# pcb.net
KiCad netlist of a schematic drawn in EAGLE
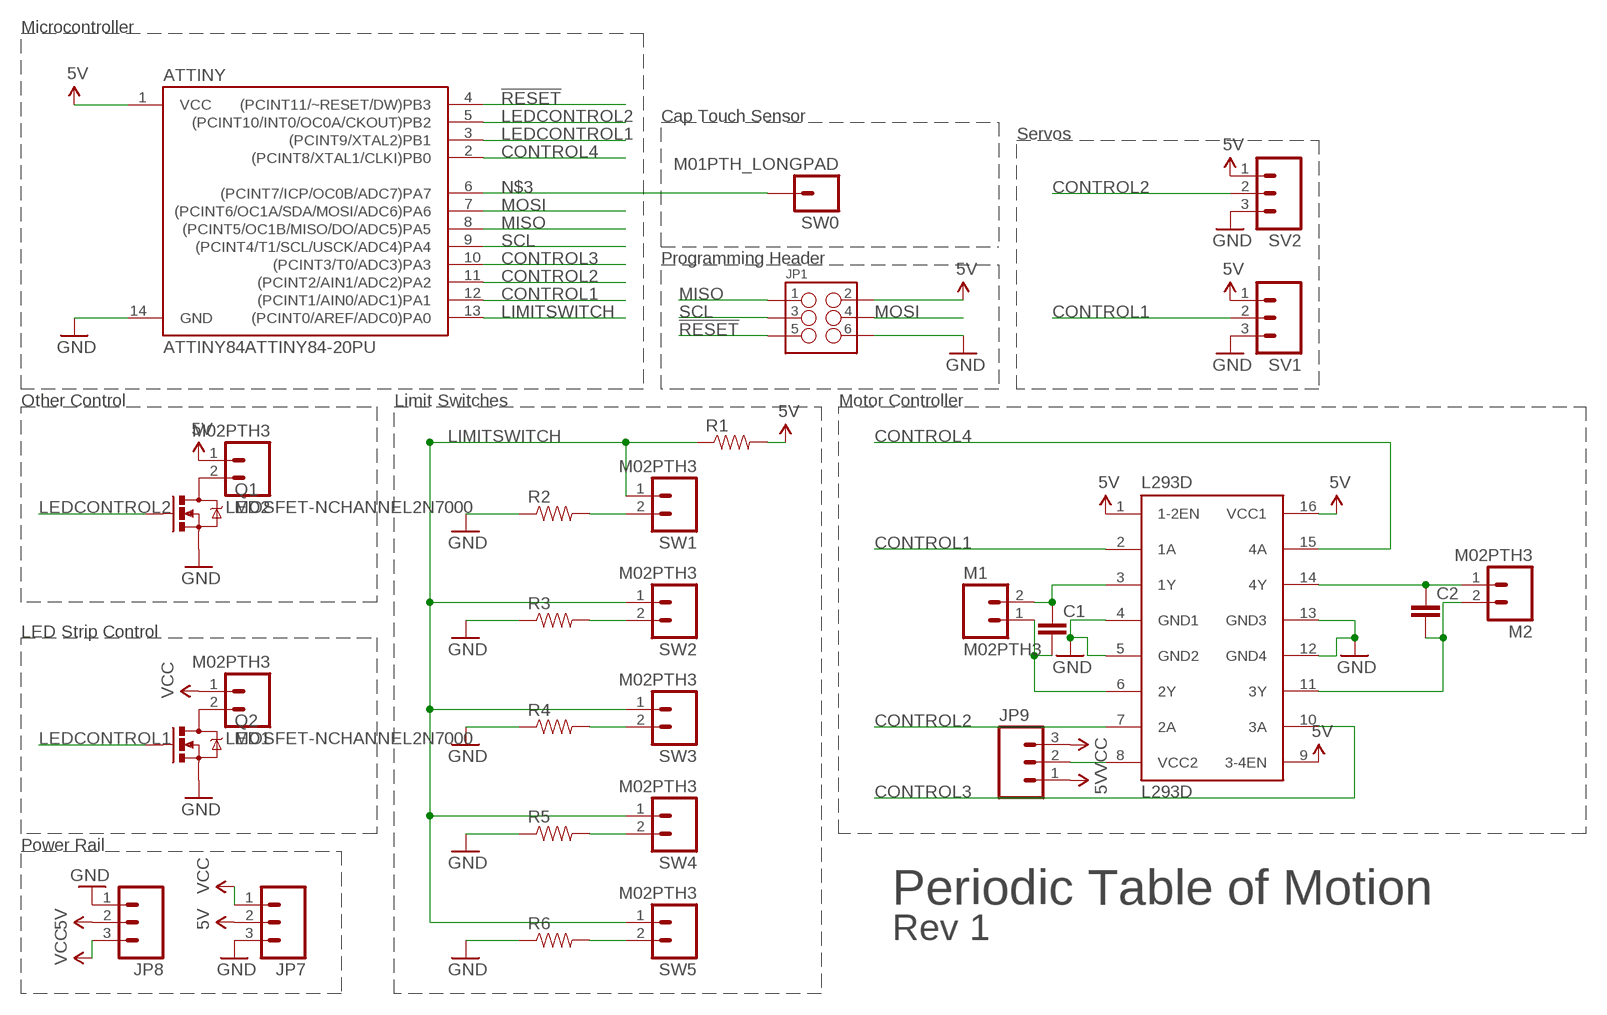
[diagram p0: schematic, sheet 1]

(export (version "E")
  (design (tool "Eeschema 10.0.6"))
  (components
    (comp (ref "ATTINY")
      (value "ATTINY84ATTINY84-20PU")
      (footprint "eagle-import:DIL14")
      (libsource (lib "eagle-import") (part "ATTINY84ATTINY84-20PU"))
    )
    (comp (ref "C1")
      (value "CAPPTH")
      (footprint "eagle-import:CAP-PTH-SMALL")
      (libsource (lib "eagle-import") (part "CAPPTH"))
    )
    (comp (ref "C2")
      (value "CAPPTH")
      (footprint "eagle-import:CAP-PTH-SMALL")
      (libsource (lib "eagle-import") (part "CAPPTH"))
    )
    (comp (ref "JP1")
      (value "M03X22X3_SILK_MALE_PTH")
      (footprint "eagle-import:2X3")
      (libsource (lib "eagle-import") (part "M03X22X3_SILK_MALE_PTH"))
    )
    (comp (ref "JP7")
      (value "M03SCREW")
      (footprint "eagle-import:SCREWTERMINAL-3.5MM-3")
      (libsource (lib "eagle-import") (part "M03SCREW"))
    )
    (comp (ref "JP8")
      (value "M03SCREW")
      (footprint "eagle-import:SCREWTERMINAL-3.5MM-3")
      (libsource (lib "eagle-import") (part "M03SCREW"))
    )
    (comp (ref "JP9")
      (value "M03LONGPADS")
      (footprint "eagle-import:1X03_LONGPADS")
      (libsource (lib "eagle-import") (part "M03LONGPADS"))
    )
    (comp (ref "L293D")
      (value "L293D")
      (footprint "eagle-import:DIL16")
      (libsource (lib "eagle-import") (part "L293D"))
    )
    (comp (ref "LED1")
      (value "M02PTH3")
      (footprint "eagle-import:1X02_LONGPADS")
      (libsource (lib "eagle-import") (part "M02PTH3"))
    )
    (comp (ref "LED2")
      (value "M02PTH3")
      (footprint "eagle-import:1X02_LONGPADS")
      (libsource (lib "eagle-import") (part "M02PTH3"))
    )
    (comp (ref "M1")
      (value "M02PTH3")
      (footprint "eagle-import:1X02_LONGPADS")
      (libsource (lib "eagle-import") (part "M02PTH3"))
    )
    (comp (ref "M2")
      (value "M02PTH3")
      (footprint "eagle-import:1X02_LONGPADS")
      (libsource (lib "eagle-import") (part "M02PTH3"))
    )
    (comp (ref "Q1")
      (value "MOSFET-NCHANNEL2N7000")
      (footprint "eagle-import:TO-92")
      (libsource (lib "eagle-import") (part "MOSFET-NCHANNEL2N7000"))
    )
    (comp (ref "Q2")
      (value "MOSFET-NCHANNEL2N7000")
      (footprint "eagle-import:TO-92")
      (libsource (lib "eagle-import") (part "MOSFET-NCHANNEL2N7000"))
    )
    (comp (ref "R1")
      (value "RESISTORPTH-1/4W")
      (footprint "eagle-import:AXIAL-0.4")
      (libsource (lib "eagle-import") (part "RESISTORPTH-1/4W"))
    )
    (comp (ref "R2")
      (value "RESISTORPTH-1/4W")
      (footprint "eagle-import:AXIAL-0.4")
      (libsource (lib "eagle-import") (part "RESISTORPTH-1/4W"))
    )
    (comp (ref "R3")
      (value "RESISTORPTH-1/4W")
      (footprint "eagle-import:AXIAL-0.4")
      (libsource (lib "eagle-import") (part "RESISTORPTH-1/4W"))
    )
    (comp (ref "R4")
      (value "RESISTORPTH-1/4W")
      (footprint "eagle-import:AXIAL-0.4")
      (libsource (lib "eagle-import") (part "RESISTORPTH-1/4W"))
    )
    (comp (ref "R5")
      (value "RESISTORPTH-1/4W")
      (footprint "eagle-import:AXIAL-0.4")
      (libsource (lib "eagle-import") (part "RESISTORPTH-1/4W"))
    )
    (comp (ref "R6")
      (value "RESISTORPTH-1/4W")
      (footprint "eagle-import:AXIAL-0.4")
      (libsource (lib "eagle-import") (part "RESISTORPTH-1/4W"))
    )
    (comp (ref "SV1")
      (value "M03LONGPADS")
      (footprint "eagle-import:1X03_LONGPADS")
      (libsource (lib "eagle-import") (part "M03LONGPADS"))
    )
    (comp (ref "SV2")
      (value "M03LONGPADS")
      (footprint "eagle-import:1X03_LONGPADS")
      (libsource (lib "eagle-import") (part "M03LONGPADS"))
    )
    (comp (ref "SW0")
      (value "M01PTH_LONGPAD")
      (footprint "eagle-import:1X01_LONGPAD")
      (libsource (lib "eagle-import") (part "M01PTH_LONGPAD"))
    )
    (comp (ref "SW1")
      (value "M02PTH3")
      (footprint "eagle-import:1X02_LONGPADS")
      (libsource (lib "eagle-import") (part "M02PTH3"))
    )
    (comp (ref "SW2")
      (value "M02PTH3")
      (footprint "eagle-import:1X02_LONGPADS")
      (libsource (lib "eagle-import") (part "M02PTH3"))
    )
    (comp (ref "SW3")
      (value "M02PTH3")
      (footprint "eagle-import:1X02_LONGPADS")
      (libsource (lib "eagle-import") (part "M02PTH3"))
    )
    (comp (ref "SW4")
      (value "M02PTH3")
      (footprint "eagle-import:1X02_LONGPADS")
      (libsource (lib "eagle-import") (part "M02PTH3"))
    )
    (comp (ref "SW5")
      (value "M02PTH3")
      (footprint "eagle-import:1X02_LONGPADS")
      (libsource (lib "eagle-import") (part "M02PTH3"))
    )
  )
  (nets
    (net (code "1") (name "/CONTROL1") (class "Default")
      (node (ref "ATTINY") (pin "12") (pinfunction "(PCINT1/AIN0/ADC1)PA1_12") (pintype "bidirectional"))
      (node (ref "L293D") (pin "2") (pinfunction "1A_2") (pintype "input"))
      (node (ref "SV1") (pin "2") (pinfunction "2_2") (pintype "passive"))
    )
    (net (code "2") (name "/CONTROL2") (class "Default")
      (node (ref "ATTINY") (pin "11") (pinfunction "(PCINT2/AIN1/ADC2)PA2_11") (pintype "bidirectional"))
      (node (ref "L293D") (pin "7") (pinfunction "2A_7") (pintype "input"))
      (node (ref "SV2") (pin "2") (pinfunction "2_2") (pintype "passive"))
    )
    (net (code "3") (name "/CONTROL3") (class "Default")
      (node (ref "ATTINY") (pin "10") (pinfunction "(PCINT3/T0/ADC3)PA3_10") (pintype "bidirectional"))
      (node (ref "L293D") (pin "10") (pinfunction "3A_10") (pintype "input"))
    )
    (net (code "4") (name "/CONTROL4") (class "Default")
      (node (ref "ATTINY") (pin "2") (pinfunction "(PCINT8/XTAL1/CLKI)PB0_2") (pintype "bidirectional"))
      (node (ref "L293D") (pin "15") (pinfunction "4A_15") (pintype "input"))
    )
    (net (code "5") (name "/LEDCONTROL1") (class "Default")
      (node (ref "ATTINY") (pin "3") (pinfunction "(PCINT9/XTAL2)PB1_3") (pintype "bidirectional"))
      (node (ref "Q2") (pin "2") (pinfunction "G_2") (pintype "passive"))
    )
    (net (code "6") (name "/LEDCONTROL2") (class "Default")
      (node (ref "ATTINY") (pin "5") (pinfunction "(PCINT10/INT0/OC0A/CKOUT)PB2_5") (pintype "bidirectional"))
      (node (ref "Q1") (pin "2") (pinfunction "G_2") (pintype "passive"))
    )
    (net (code "7") (name "/LIMITSWITCH") (class "Default")
      (node (ref "ATTINY") (pin "13") (pinfunction "(PCINT0/AREF/ADC0)PA0_13") (pintype "bidirectional"))
      (node (ref "R1") (pin "P$1") (pinfunction "1_P$1") (pintype "passive"))
      (node (ref "SW1") (pin "1") (pinfunction "1_1") (pintype "passive"))
      (node (ref "SW2") (pin "1") (pinfunction "1_1") (pintype "passive"))
      (node (ref "SW3") (pin "1") (pinfunction "1_1") (pintype "passive"))
      (node (ref "SW4") (pin "1") (pinfunction "1_1") (pintype "passive"))
      (node (ref "SW5") (pin "1") (pinfunction "1_1") (pintype "passive"))
    )
    (net (code "8") (name "/MISO") (class "Default")
      (node (ref "ATTINY") (pin "8") (pinfunction "(PCINT5/OC1B/MISO/DO/ADC5)PA5_8") (pintype "bidirectional"))
      (node (ref "JP1") (pin "1") (pinfunction "1_1") (pintype "bidirectional"))
    )
    (net (code "9") (name "/MOSI") (class "Default")
      (node (ref "ATTINY") (pin "7") (pinfunction "(PCINT6/OC1A/SDA/MOSI/ADC6)PA6_7") (pintype "bidirectional"))
      (node (ref "JP1") (pin "4") (pinfunction "4_4") (pintype "bidirectional"))
    )
    (net (code "10") (name "/N$3") (class "Default")
      (node (ref "ATTINY") (pin "6") (pinfunction "(PCINT7/ICP/OC0B/ADC7)PA7_6") (pintype "bidirectional"))
      (node (ref "SW0") (pin "1") (pinfunction "1_1") (pintype "passive"))
    )
    (net (code "11") (name "/SCL") (class "Default")
      (node (ref "ATTINY") (pin "9") (pinfunction "(PCINT4/T1/SCL/USCK/ADC4)PA4_9") (pintype "bidirectional"))
      (node (ref "JP1") (pin "3") (pinfunction "3_3") (pintype "bidirectional"))
    )
    (net (code "12") (name "/~{RESET}") (class "Default")
      (node (ref "ATTINY") (pin "4") (pinfunction "(PCINT11/~{RESET/DW})PB3_4") (pintype "bidirectional"))
      (node (ref "JP1") (pin "5") (pinfunction "5_5") (pintype "bidirectional"))
    )
    (net (code "13") (name "5V") (class "Default")
      (node (ref "ATTINY") (pin "1") (pinfunction "VCC_1") (pintype "bidirectional"))
      (node (ref "JP1") (pin "2") (pinfunction "2_2") (pintype "bidirectional"))
      (node (ref "JP7") (pin "2") (pinfunction "2_2") (pintype "passive"))
      (node (ref "JP8") (pin "2") (pinfunction "2_2") (pintype "passive"))
      (node (ref "JP9") (pin "1") (pinfunction "1_1") (pintype "passive"))
      (node (ref "L293D") (pin "1") (pinfunction "1-2EN_1") (pintype "input"))
      (node (ref "L293D") (pin "16") (pinfunction "VCC1_16") (pintype "power_in"))
      (node (ref "L293D") (pin "9") (pinfunction "3-4EN_9") (pintype "input"))
      (node (ref "LED2") (pin "1") (pinfunction "1_1") (pintype "passive"))
      (node (ref "R1") (pin "P$2") (pinfunction "2_P$2") (pintype "passive"))
      (node (ref "SV1") (pin "1") (pinfunction "1_1") (pintype "passive"))
      (node (ref "SV2") (pin "1") (pinfunction "1_1") (pintype "passive"))
    )
    (net (code "14") (name "GND") (class "Default")
      (node (ref "ATTINY") (pin "14") (pinfunction "GND_14") (pintype "bidirectional"))
      (node (ref "JP1") (pin "6") (pinfunction "6_6") (pintype "bidirectional"))
      (node (ref "JP7") (pin "3") (pinfunction "3_3") (pintype "passive"))
      (node (ref "JP8") (pin "1") (pinfunction "1_1") (pintype "passive"))
      (node (ref "L293D") (pin "12") (pinfunction "GND4_12") (pintype "power_in"))
      (node (ref "L293D") (pin "13") (pinfunction "GND3_13") (pintype "power_in"))
      (node (ref "L293D") (pin "4") (pinfunction "GND1_4") (pintype "power_in"))
      (node (ref "L293D") (pin "5") (pinfunction "GND2_5") (pintype "power_in"))
      (node (ref "Q1") (pin "1") (pinfunction "S_1") (pintype "passive"))
      (node (ref "Q2") (pin "1") (pinfunction "S_1") (pintype "passive"))
      (node (ref "R2") (pin "P$1") (pinfunction "1_P$1") (pintype "passive"))
      (node (ref "R3") (pin "P$1") (pinfunction "1_P$1") (pintype "passive"))
      (node (ref "R4") (pin "P$1") (pinfunction "1_P$1") (pintype "passive"))
      (node (ref "R5") (pin "P$1") (pinfunction "1_P$1") (pintype "passive"))
      (node (ref "R6") (pin "P$1") (pinfunction "1_P$1") (pintype "passive"))
      (node (ref "SV1") (pin "3") (pinfunction "3_3") (pintype "passive"))
      (node (ref "SV2") (pin "3") (pinfunction "3_3") (pintype "passive"))
    )
    (net (code "15") (name "Net-(L293D-1Y)") (class "Default")
      (node (ref "C1") (pin "1") (pinfunction "1_1") (pintype "passive"))
      (node (ref "L293D") (pin "3") (pinfunction "1Y_3") (pintype "output"))
      (node (ref "M1") (pin "2") (pinfunction "2_2") (pintype "passive"))
    )
    (net (code "16") (name "Net-(L293D-2Y)") (class "Default")
      (node (ref "C1") (pin "2") (pinfunction "2_2") (pintype "passive"))
      (node (ref "L293D") (pin "6") (pinfunction "2Y_6") (pintype "output"))
      (node (ref "M1") (pin "1") (pinfunction "1_1") (pintype "passive"))
    )
    (net (code "17") (name "Net-(L293D-3Y)") (class "Default")
      (node (ref "C2") (pin "2") (pinfunction "2_2") (pintype "passive"))
      (node (ref "L293D") (pin "11") (pinfunction "3Y_11") (pintype "output"))
      (node (ref "M2") (pin "2") (pinfunction "2_2") (pintype "passive"))
    )
    (net (code "18") (name "Net-(L293D-4Y)") (class "Default")
      (node (ref "C2") (pin "1") (pinfunction "1_1") (pintype "passive"))
      (node (ref "L293D") (pin "14") (pinfunction "4Y_14") (pintype "output"))
      (node (ref "M2") (pin "1") (pinfunction "1_1") (pintype "passive"))
    )
    (net (code "19") (name "Net-(L293D-VCC2)") (class "Default")
      (node (ref "JP9") (pin "2") (pinfunction "2_2") (pintype "passive"))
      (node (ref "L293D") (pin "8") (pinfunction "VCC2_8") (pintype "power_in"))
    )
    (net (code "20") (name "Net-(Q1-D)") (class "Default")
      (node (ref "LED2") (pin "2") (pinfunction "2_2") (pintype "passive"))
      (node (ref "Q1") (pin "3") (pinfunction "D_3") (pintype "passive"))
    )
    (net (code "21") (name "Net-(Q2-D)") (class "Default")
      (node (ref "LED1") (pin "2") (pinfunction "2_2") (pintype "passive"))
      (node (ref "Q2") (pin "3") (pinfunction "D_3") (pintype "passive"))
    )
    (net (code "22") (name "Net-(R2-2)") (class "Default")
      (node (ref "R2") (pin "P$2") (pinfunction "2_P$2") (pintype "passive"))
      (node (ref "SW1") (pin "2") (pinfunction "2_2") (pintype "passive"))
    )
    (net (code "23") (name "Net-(R3-2)") (class "Default")
      (node (ref "R3") (pin "P$2") (pinfunction "2_P$2") (pintype "passive"))
      (node (ref "SW2") (pin "2") (pinfunction "2_2") (pintype "passive"))
    )
    (net (code "24") (name "Net-(R4-2)") (class "Default")
      (node (ref "R4") (pin "P$2") (pinfunction "2_P$2") (pintype "passive"))
      (node (ref "SW3") (pin "2") (pinfunction "2_2") (pintype "passive"))
    )
    (net (code "25") (name "Net-(R5-2)") (class "Default")
      (node (ref "R5") (pin "P$2") (pinfunction "2_P$2") (pintype "passive"))
      (node (ref "SW4") (pin "2") (pinfunction "2_2") (pintype "passive"))
    )
    (net (code "26") (name "Net-(R6-2)") (class "Default")
      (node (ref "R6") (pin "P$2") (pinfunction "2_P$2") (pintype "passive"))
      (node (ref "SW5") (pin "2") (pinfunction "2_2") (pintype "passive"))
    )
    (net (code "27") (name "VCC") (class "Default")
      (node (ref "JP7") (pin "1") (pinfunction "1_1") (pintype "passive"))
      (node (ref "JP8") (pin "3") (pinfunction "3_3") (pintype "passive"))
      (node (ref "JP9") (pin "3") (pinfunction "3_3") (pintype "passive"))
      (node (ref "LED1") (pin "1") (pinfunction "1_1") (pintype "passive"))
    )
  )
)
